# full.net
KiCad netlist of a schematic drawn in Altium Designer
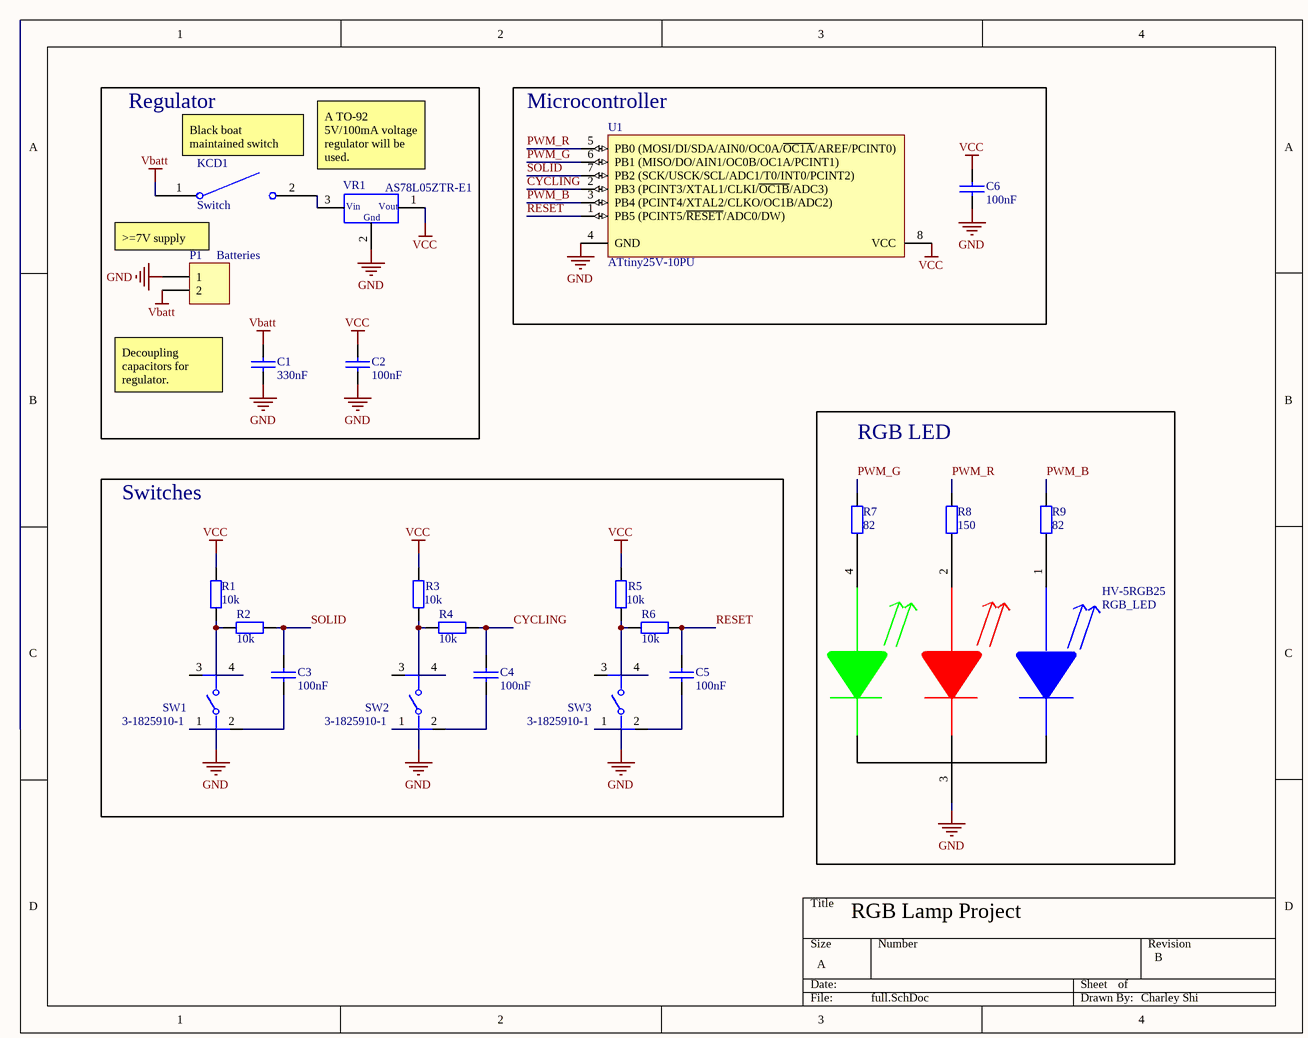
[diagram p0: full.SchDoc]

(export (version "E")
  (design (tool "Eeschema 10.0.6"))
  (components
    (comp (ref "C1")
      (value "330nF")
      (footprint "ece-RAD0.2")
      (description "Capacitor Non Polarised Through Hole")
      (libsource (lib "ece components") (part "CAP"))
    )
    (comp (ref "C2")
      (value "100nF")
      (footprint "ece-RAD0.2")
      (description "Capacitor Non Polarised Through Hole")
      (libsource (lib "ece components") (part "CAP"))
    )
    (comp (ref "C3")
      (value "100nF")
      (footprint "ece-RAD0.2")
      (description "Capacitor Non Polarised Through Hole")
      (libsource (lib "ece components") (part "CAP"))
    )
    (comp (ref "C4")
      (value "100nF")
      (footprint "ece-RAD0.2")
      (description "Capacitor Non Polarised Through Hole")
      (libsource (lib "ece components") (part "CAP"))
    )
    (comp (ref "C5")
      (value "100nF")
      (footprint "ece-RAD0.2")
      (description "Capacitor Non Polarised Through Hole")
      (libsource (lib "ece components") (part "CAP"))
    )
    (comp (ref "C6")
      (value "100nF")
      (footprint "ece-RAD0.2")
      (description "Capacitor Non Polarised Through Hole")
      (libsource (lib "ece components") (part "CAP"))
    )
    (comp (ref "HV-5RGB25")
      (value "RGB_LED")
      (footprint "HV-5RGB25")
      (libsource (lib "RGB_LED") (part "RGB_LED"))
    )
    (comp (ref "KCD1") (value "Switch") (libsource (lib "RGB_LED") (part "Switch")))
    (comp (ref "P1")
      (value "Batteries")
      (footprint "ece-HDR1X2")
      (description "Header, 2-Pin")
      (fields (field (name "PUBLISHER") "Altium Limited"))
      (libsource (lib "ece components") (part "Header 2"))
    )
    (comp (ref "R1")
      (value "10k")
      (footprint "ece-AXIAL0.4")
      (description "Resistor")
      (fields (field (name "PUBLISHER") "Altium Limited"))
      (libsource (lib "ece components") (part "Res2"))
    )
    (comp (ref "R2")
      (value "10k")
      (footprint "ece-AXIAL0.4")
      (description "Resistor")
      (fields (field (name "PUBLISHER") "Altium Limited"))
      (libsource (lib "") (part "Res2_1"))
    )
    (comp (ref "R3")
      (value "10k")
      (footprint "ece-AXIAL0.4")
      (description "Resistor")
      (fields (field (name "PUBLISHER") "Altium Limited"))
      (libsource (lib "ece components") (part "Res2"))
    )
    (comp (ref "R4")
      (value "10k")
      (footprint "ece-AXIAL0.4")
      (description "Resistor")
      (fields (field (name "PUBLISHER") "Altium Limited"))
      (libsource (lib "") (part "Res2_1"))
    )
    (comp (ref "R5")
      (value "10k")
      (footprint "ece-AXIAL0.4")
      (description "Resistor")
      (fields (field (name "PUBLISHER") "Altium Limited"))
      (libsource (lib "ece components") (part "Res2"))
    )
    (comp (ref "R6")
      (value "10k")
      (footprint "ece-AXIAL0.4")
      (description "Resistor")
      (fields (field (name "PUBLISHER") "Altium Limited"))
      (libsource (lib "") (part "Res2_1"))
    )
    (comp (ref "R7")
      (value "82")
      (footprint "ece-AXIAL0.4")
      (description "Resistor")
      (fields (field (name "PUBLISHER") "Altium Limited"))
      (libsource (lib "ece components") (part "Res2"))
    )
    (comp (ref "R8")
      (value "150")
      (footprint "ece-AXIAL0.4")
      (description "Resistor")
      (fields (field (name "PUBLISHER") "Altium Limited"))
      (libsource (lib "ece components") (part "Res2"))
    )
    (comp (ref "R9")
      (value "82")
      (footprint "ece-AXIAL0.4")
      (description "Resistor")
      (fields (field (name "PUBLISHER") "Altium Limited"))
      (libsource (lib "ece components") (part "Res2"))
    )
    (comp (ref "SW1")
      (value "3-1825910-1")
      (footprint "FP-3-1825910-1-MFG")
      (description "SWITCH TACTILE SPST-NO 0.05A 24V")
      (fields
        (field (name "MANUFACTURER") "TE Connectivity")
        (field (name "OCTOPART") "https://octopart.com/3-1825910-1-te+connectivity-46506874")
      )
      (libsource (lib "Altium Content Vault") (part "b8895f3f4cefb76e1819d2863dba89b"))
    )
    (comp (ref "SW2")
      (value "3-1825910-1")
      (footprint "FP-3-1825910-1-MFG")
      (description "SWITCH TACTILE SPST-NO 0.05A 24V")
      (fields
        (field (name "MANUFACTURER") "TE Connectivity")
        (field (name "OCTOPART") "https://octopart.com/3-1825910-1-te+connectivity-46506874")
      )
      (libsource (lib "Altium Content Vault") (part "b8895f3f4cefb76e1819d2863dba89b"))
    )
    (comp (ref "SW3")
      (value "3-1825910-1")
      (footprint "FP-3-1825910-1-MFG")
      (description "SWITCH TACTILE SPST-NO 0.05A 24V")
      (fields
        (field (name "MANUFACTURER") "TE Connectivity")
        (field (name "OCTOPART") "https://octopart.com/3-1825910-1-te+connectivity-46506874")
      )
      (libsource (lib "Altium Content Vault") (part "b8895f3f4cefb76e1819d2863dba89b"))
    )
    (comp (ref "U1")
      (value "ATtiny25V-10PU")
      (footprint "8P3")
      (libsource (lib "Altium Content Vault") (part "MC-8B-ATT25-IL8"))
    )
    (comp (ref "VR1")
      (value "AS78L05ZTR-E1")
      (footprint "ece-TO-92")
      (description "Voltage Regulator")
      (libsource (lib "ece components") (part "VoltRegSmall"))
    )
  )
  (nets
    (net (code "1") (name "/CYCLING") (class "Default")
      (node (ref "C4") (pin "1") (pinfunction "1_1") (pintype "passive"))
      (node (ref "R4") (pin "2") (pinfunction "2_2") (pintype "passive"))
      (node (ref "U1") (pin "2") (pinfunction "PB3_(PCINT3/XTAL1/CLKI/~{OC1B}/ADC3)_2") (pintype "bidirectional"))
    )
    (net (code "2") (name "/PWM_B") (class "Default")
      (node (ref "R9") (pin "2") (pinfunction "2_2") (pintype "passive"))
      (node (ref "U1") (pin "3") (pinfunction "PB4_(PCINT4/XTAL2/CLKO/OC1B/ADC2)_3") (pintype "bidirectional"))
    )
    (net (code "3") (name "/PWM_G") (class "Default")
      (node (ref "R7") (pin "2") (pinfunction "2_2") (pintype "passive"))
      (node (ref "U1") (pin "6") (pinfunction "PB1_(MISO/DO/AIN1/OC0B/OC1A/PCINT1)_6") (pintype "bidirectional"))
    )
    (net (code "4") (name "/PWM_R") (class "Default")
      (node (ref "R8") (pin "2") (pinfunction "2_2") (pintype "passive"))
      (node (ref "U1") (pin "5") (pinfunction "PB0_(MOSI/DI/SDA/AIN0/OC0A/~{OC1A}/AREF/PCINT0)_5") (pintype "bidirectional"))
    )
    (net (code "5") (name "/RESET") (class "Default")
      (node (ref "C5") (pin "1") (pinfunction "1_1") (pintype "passive"))
      (node (ref "R6") (pin "2") (pinfunction "2_2") (pintype "passive"))
      (node (ref "U1") (pin "1") (pinfunction "PB5_(PCINT5/~{RESET}/ADC0/DW)_1") (pintype "bidirectional"))
    )
    (net (code "6") (name "/SOLID") (class "Default")
      (node (ref "C3") (pin "1") (pinfunction "1_1") (pintype "passive"))
      (node (ref "R2") (pin "2") (pinfunction "2_2") (pintype "passive"))
      (node (ref "U1") (pin "7") (pinfunction "PB2_(SCK/USCK/SCL/ADC1/T0/INT0/PCINT2)_7") (pintype "bidirectional"))
    )
    (net (code "7") (name "GND") (class "Default")
      (node (ref "C1") (pin "2") (pinfunction "2_2") (pintype "passive"))
      (node (ref "C2") (pin "2") (pinfunction "2_2") (pintype "passive"))
      (node (ref "C6") (pin "2") (pinfunction "2_2") (pintype "passive"))
      (node (ref "HV-5RGB25") (pin "3") (pinfunction "(COM)_3") (pintype "passive"))
      (node (ref "P1") (pin "1") (pinfunction "1_1") (pintype "passive"))
      (node (ref "SW1") (pin "1") (pinfunction "1_1") (pintype "passive"))
      (node (ref "SW2") (pin "1") (pinfunction "1_1") (pintype "passive"))
      (node (ref "SW3") (pin "1") (pinfunction "1_1") (pintype "passive"))
      (node (ref "U1") (pin "4") (pinfunction "GND_4") (pintype "power_in"))
      (node (ref "VR1") (pin "2") (pinfunction "Gnd_2") (pintype "passive"))
    )
    (net (code "8") (name "Net-(C3-Pad2)") (class "Default")
      (node (ref "C3") (pin "2") (pinfunction "2_2") (pintype "passive"))
      (node (ref "SW1") (pin "2") (pinfunction "2_2") (pintype "passive"))
    )
    (net (code "9") (name "Net-(C4-Pad2)") (class "Default")
      (node (ref "C4") (pin "2") (pinfunction "2_2") (pintype "passive"))
      (node (ref "SW2") (pin "2") (pinfunction "2_2") (pintype "passive"))
    )
    (net (code "10") (name "Net-(C5-Pad2)") (class "Default")
      (node (ref "C5") (pin "2") (pinfunction "2_2") (pintype "passive"))
      (node (ref "SW3") (pin "2") (pinfunction "2_2") (pintype "passive"))
    )
    (net (code "11") (name "Net-(HV-5RGB25-B)") (class "Default")
      (node (ref "HV-5RGB25") (pin "1") (pinfunction "B_1") (pintype "passive"))
      (node (ref "R9") (pin "1") (pinfunction "1_1") (pintype "passive"))
    )
    (net (code "12") (name "Net-(HV-5RGB25-G)") (class "Default")
      (node (ref "HV-5RGB25") (pin "4") (pinfunction "G_4") (pintype "passive"))
      (node (ref "R7") (pin "1") (pinfunction "1_1") (pintype "passive"))
    )
    (net (code "13") (name "Net-(HV-5RGB25-R)") (class "Default")
      (node (ref "HV-5RGB25") (pin "2") (pinfunction "R_2") (pintype "passive"))
      (node (ref "R8") (pin "1") (pinfunction "1_1") (pintype "passive"))
    )
    (net (code "14") (name "Net-(R1-Pad1)") (class "Default")
      (node (ref "R1") (pin "1") (pinfunction "1_1") (pintype "passive"))
      (node (ref "R2") (pin "1") (pinfunction "1_1") (pintype "passive"))
      (node (ref "SW1") (pin "4") (pinfunction "4_4") (pintype "passive"))
    )
    (net (code "15") (name "Net-(R3-Pad1)") (class "Default")
      (node (ref "R3") (pin "1") (pinfunction "1_1") (pintype "passive"))
      (node (ref "R4") (pin "1") (pinfunction "1_1") (pintype "passive"))
      (node (ref "SW2") (pin "4") (pinfunction "4_4") (pintype "passive"))
    )
    (net (code "16") (name "Net-(R5-Pad1)") (class "Default")
      (node (ref "R5") (pin "1") (pinfunction "1_1") (pintype "passive"))
      (node (ref "R6") (pin "1") (pinfunction "1_1") (pintype "passive"))
      (node (ref "SW3") (pin "4") (pinfunction "4_4") (pintype "passive"))
    )
    (net (code "17") (name "Net-(VR1-Vin)") (class "Default")
      (node (ref "KCD1") (pin "2") (pinfunction "2_2") (pintype "passive"))
      (node (ref "VR1") (pin "3") (pinfunction "Vin_3") (pintype "passive"))
    )
    (net (code "18") (name "VCC") (class "Default")
      (node (ref "C2") (pin "1") (pinfunction "1_1") (pintype "passive"))
      (node (ref "C6") (pin "1") (pinfunction "1_1") (pintype "passive"))
      (node (ref "R1") (pin "2") (pinfunction "2_2") (pintype "passive"))
      (node (ref "R3") (pin "2") (pinfunction "2_2") (pintype "passive"))
      (node (ref "R5") (pin "2") (pinfunction "2_2") (pintype "passive"))
      (node (ref "U1") (pin "8") (pinfunction "VCC_8") (pintype "power_in"))
      (node (ref "VR1") (pin "1") (pinfunction "Vout_1") (pintype "passive"))
    )
    (net (code "19") (name "Vbatt") (class "Default")
      (node (ref "C1") (pin "1") (pinfunction "1_1") (pintype "passive"))
      (node (ref "KCD1") (pin "1") (pinfunction "1_1") (pintype "passive"))
      (node (ref "P1") (pin "2") (pinfunction "2_2") (pintype "passive"))
    )
    (net (code "20") (name "unconnected-(SW1-Pad3)") (class "Default")
      (node (ref "SW1") (pin "3") (pinfunction "3_3") (pintype "passive"))
    )
    (net (code "21") (name "unconnected-(SW2-Pad3)") (class "Default")
      (node (ref "SW2") (pin "3") (pinfunction "3_3") (pintype "passive"))
    )
    (net (code "22") (name "unconnected-(SW3-Pad3)") (class "Default")
      (node (ref "SW3") (pin "3") (pinfunction "3_3") (pintype "passive"))
    )
  )
)
